# easyeda_system.net
KiCad netlist of a schematic drawn in EasyEDA
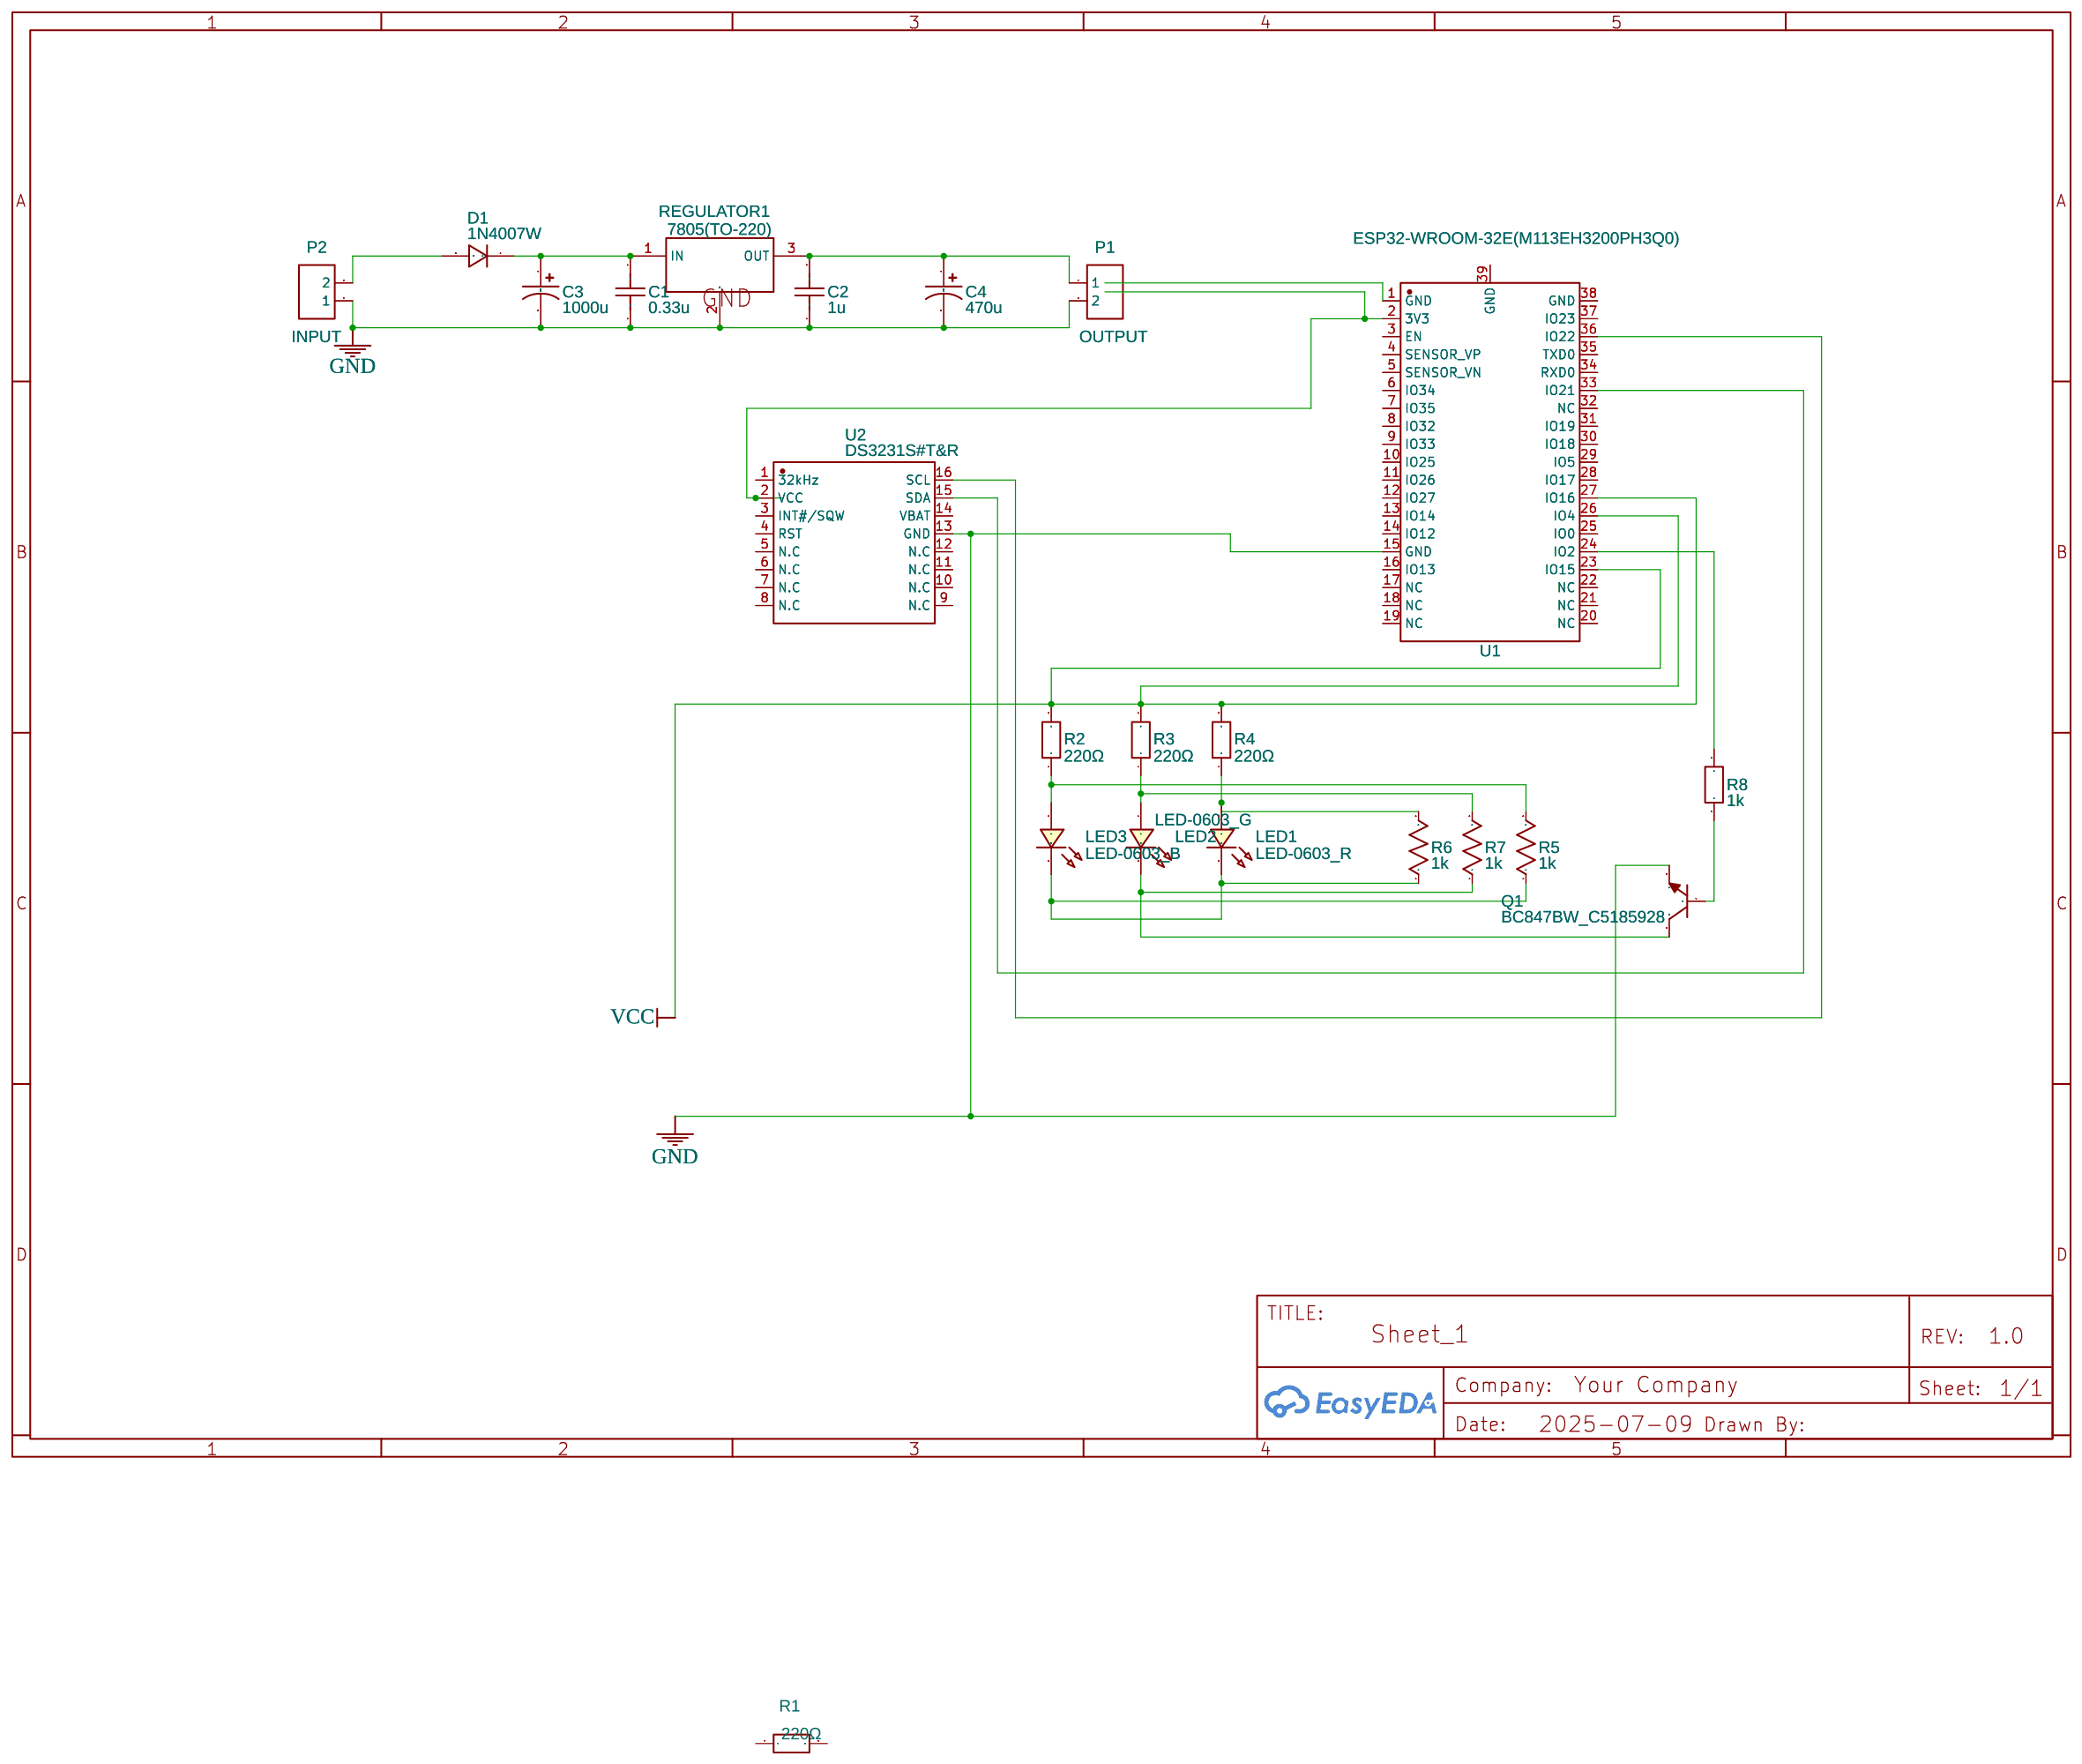
[diagram p0: schematic sheet]

(export (version "E")
  (design (tool "Eeschema 10.0.6"))
  (components
    (comp (ref "C1") (value "0.33u") (libsource (lib "") (part "C_RAD-0.1_US")))
    (comp (ref "C2") (value "1u") (libsource (lib "") (part "C_RAD-0.1_US_1")))
    (comp (ref "C3") (value "1000u") (libsource (lib "") (part "CE_TH_D3.0×F1.5_US")))
    (comp (ref "C4") (value "470u") (libsource (lib "") (part "CE_TH_D3.0×F1.5_US")))
    (comp (ref "D1")
      (value "1N4007W")
      (fields (field (name "Manufacturer") "BLUE ROCKET"))
      (libsource (lib "") (part "1N4007W"))
    )
    (comp (ref "LED1")
      (value "LED-0603_R")
      (fields
        (field (name "Manufacturer Part") "19-217/R6C-AL1M2VY/3T")
        (field (name "Manufacturer") "EVERLIGHT(台湾亿光)")
      )
      (libsource (lib "") (part "LED-0603_R"))
    )
    (comp (ref "LED2")
      (value "LED-0603_G")
      (fields
        (field (name "Manufacturer Part") "19-217/GHC-YR1S2/3T")
        (field (name "Manufacturer") "EVERLIGHT(台湾亿光)")
      )
      (libsource (lib "") (part "LED-0603_G"))
    )
    (comp (ref "LED3")
      (value "LED-0603_B")
      (fields
        (field (name "Manufacturer Part") "19-217/BHC-ZL1M2RY/3T")
        (field (name "Manufacturer") "EVERLIGHT(台湾亿光)")
      )
      (libsource (lib "") (part "LED-0603_B"))
    )
    (comp (ref "P1") (value "OUTPUT") (libsource (lib "") (part "CONN-TH_2P-P5.00_1")))
    (comp (ref "P2") (value "INPUT") (libsource (lib "") (part "CONN-TH_2P-P5.00")))
    (comp (ref "Q1")
      (value "BC847BW_C5185928")
      (fields (field (name "Manufacturer Part") "BC847BW") (field (name "Manufacturer") "Slkor(萨科微)"))
      (libsource (lib "") (part "BC847BW_C5185928"))
    )
    (comp (ref "R1")
      (value "220Ω")
      (fields (field (name "Manufacturer Part") "RWS10 220R J TR") (field (name "Manufacturer") "Ohmite"))
      (libsource (lib "") (part "RWS10 220R J TR_1"))
    )
    (comp (ref "R2")
      (value "220Ω")
      (fields (field (name "Manufacturer Part") "RWS10 220R J TR") (field (name "Manufacturer") "Ohmite"))
      (libsource (lib "") (part "RWS10 220R J TR"))
    )
    (comp (ref "R3")
      (value "220Ω")
      (fields (field (name "Manufacturer Part") "RWS10 220R J TR") (field (name "Manufacturer") "Ohmite"))
      (libsource (lib "") (part "RWS10 220R J TR"))
    )
    (comp (ref "R4")
      (value "220Ω")
      (fields (field (name "Manufacturer Part") "RWS10 220R J TR") (field (name "Manufacturer") "Ohmite"))
      (libsource (lib "") (part "RWS10 220R J TR"))
    )
    (comp (ref "R5") (value "1k") (libsource (lib "") (part "R_0603_US")))
    (comp (ref "R6") (value "1k") (libsource (lib "") (part "R_0603_US")))
    (comp (ref "R7") (value "1k") (libsource (lib "") (part "R_0603_US")))
    (comp (ref "R8") (value "1k") (libsource (lib "") (part "R_0603_EU")))
    (comp (ref "REGULATOR1")
      (value "7805(TO-220)")
      (fields
        (field (name "Manufacturer Part") "L7805CV-DG")
        (field (name "Manufacturer") "STMicroelectronics")
      )
      (libsource (lib "") (part "7805(TO-220)"))
    )
    (comp (ref "U1")
      (value "ESP32-WROOM-32E(M113EH3200PH3Q0)")
      (fields (field (name "Manufacturer") "ESPRESSIF(乐鑫)"))
      (libsource (lib "") (part "ESP32-WROOM-32E(M113EH3200PH3Q0)"))
    )
    (comp (ref "U2")
      (value "DS3231S#T&R")
      (fields (field (name "Manufacturer") "ADI(亚德诺)/MAXIM(美信)"))
      (libsource (lib "") (part "DS3231S#T&amp;R"))
    )
  )
  (nets
    (net (code "1") (name "GND") (class "Default")
      (node (ref "C1") (pin "2") (pinfunction "2_2") (pintype "unspecified"))
      (node (ref "C2") (pin "1") (pinfunction "1_1") (pintype "unspecified"))
      (node (ref "C3") (pin "2") (pinfunction "2_2") (pintype "unspecified"))
      (node (ref "C4") (pin "2") (pinfunction "2_2") (pintype "unspecified"))
      (node (ref "P1") (pin "2") (pinfunction "2_2") (pintype "unspecified"))
      (node (ref "P2") (pin "1") (pinfunction "1_1") (pintype "unspecified"))
      (node (ref "Q1") (pin "2") (pinfunction "E_2") (pintype "unspecified"))
      (node (ref "REGULATOR1") (pin "2") (pinfunction "GND_2") (pintype "passive"))
      (node (ref "U1") (pin "15") (pinfunction "GND_15") (pintype "unspecified"))
      (node (ref "U2") (pin "13") (pinfunction "GND_13") (pintype "unspecified"))
    )
    (net (code "2") (name "Net-(D1-Pad2)") (class "Default")
      (node (ref "D1") (pin "2") (pinfunction "2_2") (pintype "unspecified"))
      (node (ref "P2") (pin "2") (pinfunction "2_2") (pintype "unspecified"))
    )
    (net (code "3") (name "Net-(LED1-Pad1)") (class "Default")
      (node (ref "LED1") (pin "1") (pinfunction "1_1") (pintype "unspecified"))
      (node (ref "R4") (pin "1") (pinfunction "1_1") (pintype "unspecified"))
      (node (ref "R6") (pin "2") (pinfunction "2_2") (pintype "unspecified"))
    )
    (net (code "4") (name "Net-(LED1-Pad2)") (class "Default")
      (node (ref "LED1") (pin "2") (pinfunction "2_2") (pintype "unspecified"))
      (node (ref "LED3") (pin "2") (pinfunction "2_2") (pintype "unspecified"))
      (node (ref "R5") (pin "1") (pinfunction "1_1") (pintype "unspecified"))
      (node (ref "R6") (pin "1") (pinfunction "1_1") (pintype "unspecified"))
    )
    (net (code "5") (name "Net-(LED2-Pad1)") (class "Default")
      (node (ref "LED2") (pin "1") (pinfunction "1_1") (pintype "unspecified"))
      (node (ref "R3") (pin "1") (pinfunction "1_1") (pintype "unspecified"))
      (node (ref "R7") (pin "2") (pinfunction "2_2") (pintype "unspecified"))
    )
    (net (code "6") (name "Net-(LED3-Pad1)") (class "Default")
      (node (ref "LED3") (pin "1") (pinfunction "1_1") (pintype "unspecified"))
      (node (ref "R2") (pin "1") (pinfunction "1_1") (pintype "unspecified"))
      (node (ref "R5") (pin "2") (pinfunction "2_2") (pintype "unspecified"))
    )
    (net (code "7") (name "Net-(Q1-B)") (class "Default")
      (node (ref "Q1") (pin "1") (pinfunction "B_1") (pintype "unspecified"))
      (node (ref "R8") (pin "1") (pinfunction "1_1") (pintype "unspecified"))
    )
    (net (code "8") (name "Net-(Q1-C)") (class "Default")
      (node (ref "LED2") (pin "2") (pinfunction "2_2") (pintype "unspecified"))
      (node (ref "Q1") (pin "3") (pinfunction "C_3") (pintype "unspecified"))
      (node (ref "R7") (pin "1") (pinfunction "1_1") (pintype "unspecified"))
    )
    (net (code "9") (name "Net-(REGULATOR1-IN)") (class "Default")
      (node (ref "C1") (pin "1") (pinfunction "1_1") (pintype "unspecified"))
      (node (ref "C3") (pin "1") (pinfunction "1_1") (pintype "unspecified"))
      (node (ref "D1") (pin "1") (pinfunction "1_1") (pintype "unspecified"))
      (node (ref "REGULATOR1") (pin "1") (pinfunction "IN_1") (pintype "passive"))
    )
    (net (code "10") (name "Net-(REGULATOR1-OUT)") (class "Default")
      (node (ref "C2") (pin "2") (pinfunction "2_2") (pintype "unspecified"))
      (node (ref "C4") (pin "1") (pinfunction "1_1") (pintype "unspecified"))
      (node (ref "P1") (pin "1") (pinfunction "1_1") (pintype "unspecified"))
      (node (ref "REGULATOR1") (pin "3") (pinfunction "OUT_3") (pintype "passive"))
    )
    (net (code "11") (name "Net-(U1-3V3)") (class "Default")
      (node (ref "U1") (pin "2") (pinfunction "3V3_2") (pintype "unspecified"))
      (node (ref "U2") (pin "2") (pinfunction "VCC_2") (pintype "unspecified"))
    )
    (net (code "12") (name "Net-(U1-IO2)") (class "Default")
      (node (ref "R8") (pin "2") (pinfunction "2_2") (pintype "unspecified"))
      (node (ref "U1") (pin "24") (pinfunction "IO2_24") (pintype "unspecified"))
    )
    (net (code "13") (name "Net-(U1-IO21)") (class "Default")
      (node (ref "U1") (pin "33") (pinfunction "IO21_33") (pintype "unspecified"))
      (node (ref "U2") (pin "15") (pinfunction "SDA_15") (pintype "unspecified"))
    )
    (net (code "14") (name "Net-(U1-IO22)") (class "Default")
      (node (ref "U1") (pin "36") (pinfunction "IO22_36") (pintype "unspecified"))
      (node (ref "U2") (pin "16") (pinfunction "SCL_16") (pintype "unspecified"))
    )
    (net (code "15") (name "VCC") (class "Default")
      (node (ref "R2") (pin "2") (pinfunction "2_2") (pintype "unspecified"))
      (node (ref "R3") (pin "2") (pinfunction "2_2") (pintype "unspecified"))
      (node (ref "R4") (pin "2") (pinfunction "2_2") (pintype "unspecified"))
      (node (ref "U1") (pin "23") (pinfunction "IO15_23") (pintype "unspecified"))
      (node (ref "U1") (pin "26") (pinfunction "IO4_26") (pintype "unspecified"))
      (node (ref "U1") (pin "27") (pinfunction "IO16_27") (pintype "unspecified"))
    )
    (net (code "16") (name "unconnected-(R1-Pad1)") (class "Default")
      (node (ref "R1") (pin "1") (pinfunction "1_1") (pintype "unspecified"))
    )
    (net (code "17") (name "unconnected-(R1-Pad2)") (class "Default")
      (node (ref "R1") (pin "2") (pinfunction "2_2") (pintype "unspecified"))
    )
    (net (code "18") (name "unconnected-(U1-EN-Pad3)") (class "Default")
      (node (ref "U1") (pin "3") (pinfunction "EN_3") (pintype "unspecified"))
    )
    (net (code "19") (name "unconnected-(U1-GND-Pad1)") (class "Default")
      (node (ref "U1") (pin "1") (pinfunction "GND_1") (pintype "unspecified"))
    )
    (net (code "20") (name "unconnected-(U1-GND-Pad38)") (class "Default")
      (node (ref "U1") (pin "38") (pinfunction "GND_38") (pintype "unspecified"))
    )
    (net (code "21") (name "unconnected-(U1-GND-Pad39)") (class "Default")
      (node (ref "U1") (pin "39") (pinfunction "GND_39") (pintype "unspecified"))
    )
    (net (code "22") (name "unconnected-(U1-IO0-Pad25)") (class "Default")
      (node (ref "U1") (pin "25") (pinfunction "IO0_25") (pintype "unspecified"))
    )
    (net (code "23") (name "unconnected-(U1-IO5-Pad29)") (class "Default")
      (node (ref "U1") (pin "29") (pinfunction "IO5_29") (pintype "unspecified"))
    )
    (net (code "24") (name "unconnected-(U1-IO12-Pad14)") (class "Default")
      (node (ref "U1") (pin "14") (pinfunction "IO12_14") (pintype "unspecified"))
    )
    (net (code "25") (name "unconnected-(U1-IO13-Pad16)") (class "Default")
      (node (ref "U1") (pin "16") (pinfunction "IO13_16") (pintype "unspecified"))
    )
    (net (code "26") (name "unconnected-(U1-IO14-Pad13)") (class "Default")
      (node (ref "U1") (pin "13") (pinfunction "IO14_13") (pintype "unspecified"))
    )
    (net (code "27") (name "unconnected-(U1-IO17-Pad28)") (class "Default")
      (node (ref "U1") (pin "28") (pinfunction "IO17_28") (pintype "unspecified"))
    )
    (net (code "28") (name "unconnected-(U1-IO18-Pad30)") (class "Default")
      (node (ref "U1") (pin "30") (pinfunction "IO18_30") (pintype "unspecified"))
    )
    (net (code "29") (name "unconnected-(U1-IO19-Pad31)") (class "Default")
      (node (ref "U1") (pin "31") (pinfunction "IO19_31") (pintype "unspecified"))
    )
    (net (code "30") (name "unconnected-(U1-IO23-Pad37)") (class "Default")
      (node (ref "U1") (pin "37") (pinfunction "IO23_37") (pintype "unspecified"))
    )
    (net (code "31") (name "unconnected-(U1-IO25-Pad10)") (class "Default")
      (node (ref "U1") (pin "10") (pinfunction "IO25_10") (pintype "unspecified"))
    )
    (net (code "32") (name "unconnected-(U1-IO26-Pad11)") (class "Default")
      (node (ref "U1") (pin "11") (pinfunction "IO26_11") (pintype "unspecified"))
    )
    (net (code "33") (name "unconnected-(U1-IO27-Pad12)") (class "Default")
      (node (ref "U1") (pin "12") (pinfunction "IO27_12") (pintype "unspecified"))
    )
    (net (code "34") (name "unconnected-(U1-IO32-Pad8)") (class "Default")
      (node (ref "U1") (pin "8") (pinfunction "IO32_8") (pintype "unspecified"))
    )
    (net (code "35") (name "unconnected-(U1-IO33-Pad9)") (class "Default")
      (node (ref "U1") (pin "9") (pinfunction "IO33_9") (pintype "unspecified"))
    )
    (net (code "36") (name "unconnected-(U1-IO34-Pad6)") (class "Default")
      (node (ref "U1") (pin "6") (pinfunction "IO34_6") (pintype "unspecified"))
    )
    (net (code "37") (name "unconnected-(U1-IO35-Pad7)") (class "Default")
      (node (ref "U1") (pin "7") (pinfunction "IO35_7") (pintype "unspecified"))
    )
    (net (code "38") (name "unconnected-(U1-NC-Pad17)") (class "Default")
      (node (ref "U1") (pin "17") (pinfunction "NC_17") (pintype "unspecified"))
    )
    (net (code "39") (name "unconnected-(U1-NC-Pad18)") (class "Default")
      (node (ref "U1") (pin "18") (pinfunction "NC_18") (pintype "unspecified"))
    )
    (net (code "40") (name "unconnected-(U1-NC-Pad19)") (class "Default")
      (node (ref "U1") (pin "19") (pinfunction "NC_19") (pintype "unspecified"))
    )
    (net (code "41") (name "unconnected-(U1-NC-Pad20)") (class "Default")
      (node (ref "U1") (pin "20") (pinfunction "NC_20") (pintype "unspecified"))
    )
    (net (code "42") (name "unconnected-(U1-NC-Pad21)") (class "Default")
      (node (ref "U1") (pin "21") (pinfunction "NC_21") (pintype "unspecified"))
    )
    (net (code "43") (name "unconnected-(U1-NC-Pad22)") (class "Default")
      (node (ref "U1") (pin "22") (pinfunction "NC_22") (pintype "unspecified"))
    )
    (net (code "44") (name "unconnected-(U1-NC-Pad32)") (class "Default")
      (node (ref "U1") (pin "32") (pinfunction "NC_32") (pintype "unspecified"))
    )
    (net (code "45") (name "unconnected-(U1-RXD0-Pad34)") (class "Default")
      (node (ref "U1") (pin "34") (pinfunction "RXD0_34") (pintype "unspecified"))
    )
    (net (code "46") (name "unconnected-(U1-SENSOR_VN-Pad5)") (class "Default")
      (node (ref "U1") (pin "5") (pinfunction "SENSOR_VN_5") (pintype "unspecified"))
    )
    (net (code "47") (name "unconnected-(U1-SENSOR_VP-Pad4)") (class "Default")
      (node (ref "U1") (pin "4") (pinfunction "SENSOR_VP_4") (pintype "unspecified"))
    )
    (net (code "48") (name "unconnected-(U1-TXD0-Pad35)") (class "Default")
      (node (ref "U1") (pin "35") (pinfunction "TXD0_35") (pintype "unspecified"))
    )
    (net (code "49") (name "unconnected-(U2-32kHz-Pad1)") (class "Default")
      (node (ref "U2") (pin "1") (pinfunction "32kHz_1") (pintype "unspecified"))
    )
    (net (code "50") (name "unconnected-(U2-INT#{slash}SQW-Pad3)") (class "Default")
      (node (ref "U2") (pin "3") (pinfunction "INT#/SQW_3") (pintype "unspecified"))
    )
    (net (code "51") (name "unconnected-(U2-N.C-Pad5)") (class "Default")
      (node (ref "U2") (pin "5") (pinfunction "N.C_5") (pintype "unspecified"))
    )
    (net (code "52") (name "unconnected-(U2-N.C-Pad6)") (class "Default")
      (node (ref "U2") (pin "6") (pinfunction "N.C_6") (pintype "unspecified"))
    )
    (net (code "53") (name "unconnected-(U2-N.C-Pad7)") (class "Default")
      (node (ref "U2") (pin "7") (pinfunction "N.C_7") (pintype "unspecified"))
    )
    (net (code "54") (name "unconnected-(U2-N.C-Pad8)") (class "Default")
      (node (ref "U2") (pin "8") (pinfunction "N.C_8") (pintype "unspecified"))
    )
    (net (code "55") (name "unconnected-(U2-N.C-Pad9)") (class "Default")
      (node (ref "U2") (pin "9") (pinfunction "N.C_9") (pintype "unspecified"))
    )
    (net (code "56") (name "unconnected-(U2-N.C-Pad10)") (class "Default")
      (node (ref "U2") (pin "10") (pinfunction "N.C_10") (pintype "unspecified"))
    )
    (net (code "57") (name "unconnected-(U2-N.C-Pad11)") (class "Default")
      (node (ref "U2") (pin "11") (pinfunction "N.C_11") (pintype "unspecified"))
    )
    (net (code "58") (name "unconnected-(U2-N.C-Pad12)") (class "Default")
      (node (ref "U2") (pin "12") (pinfunction "N.C_12") (pintype "unspecified"))
    )
    (net (code "59") (name "unconnected-(U2-RST-Pad4)") (class "Default")
      (node (ref "U2") (pin "4") (pinfunction "RST_4") (pintype "unspecified"))
    )
    (net (code "60") (name "unconnected-(U2-VBAT-Pad14)") (class "Default")
      (node (ref "U2") (pin "14") (pinfunction "VBAT_14") (pintype "unspecified"))
    )
  )
)
